# Power.net
KiCad netlist of a schematic drawn in Altium Designer
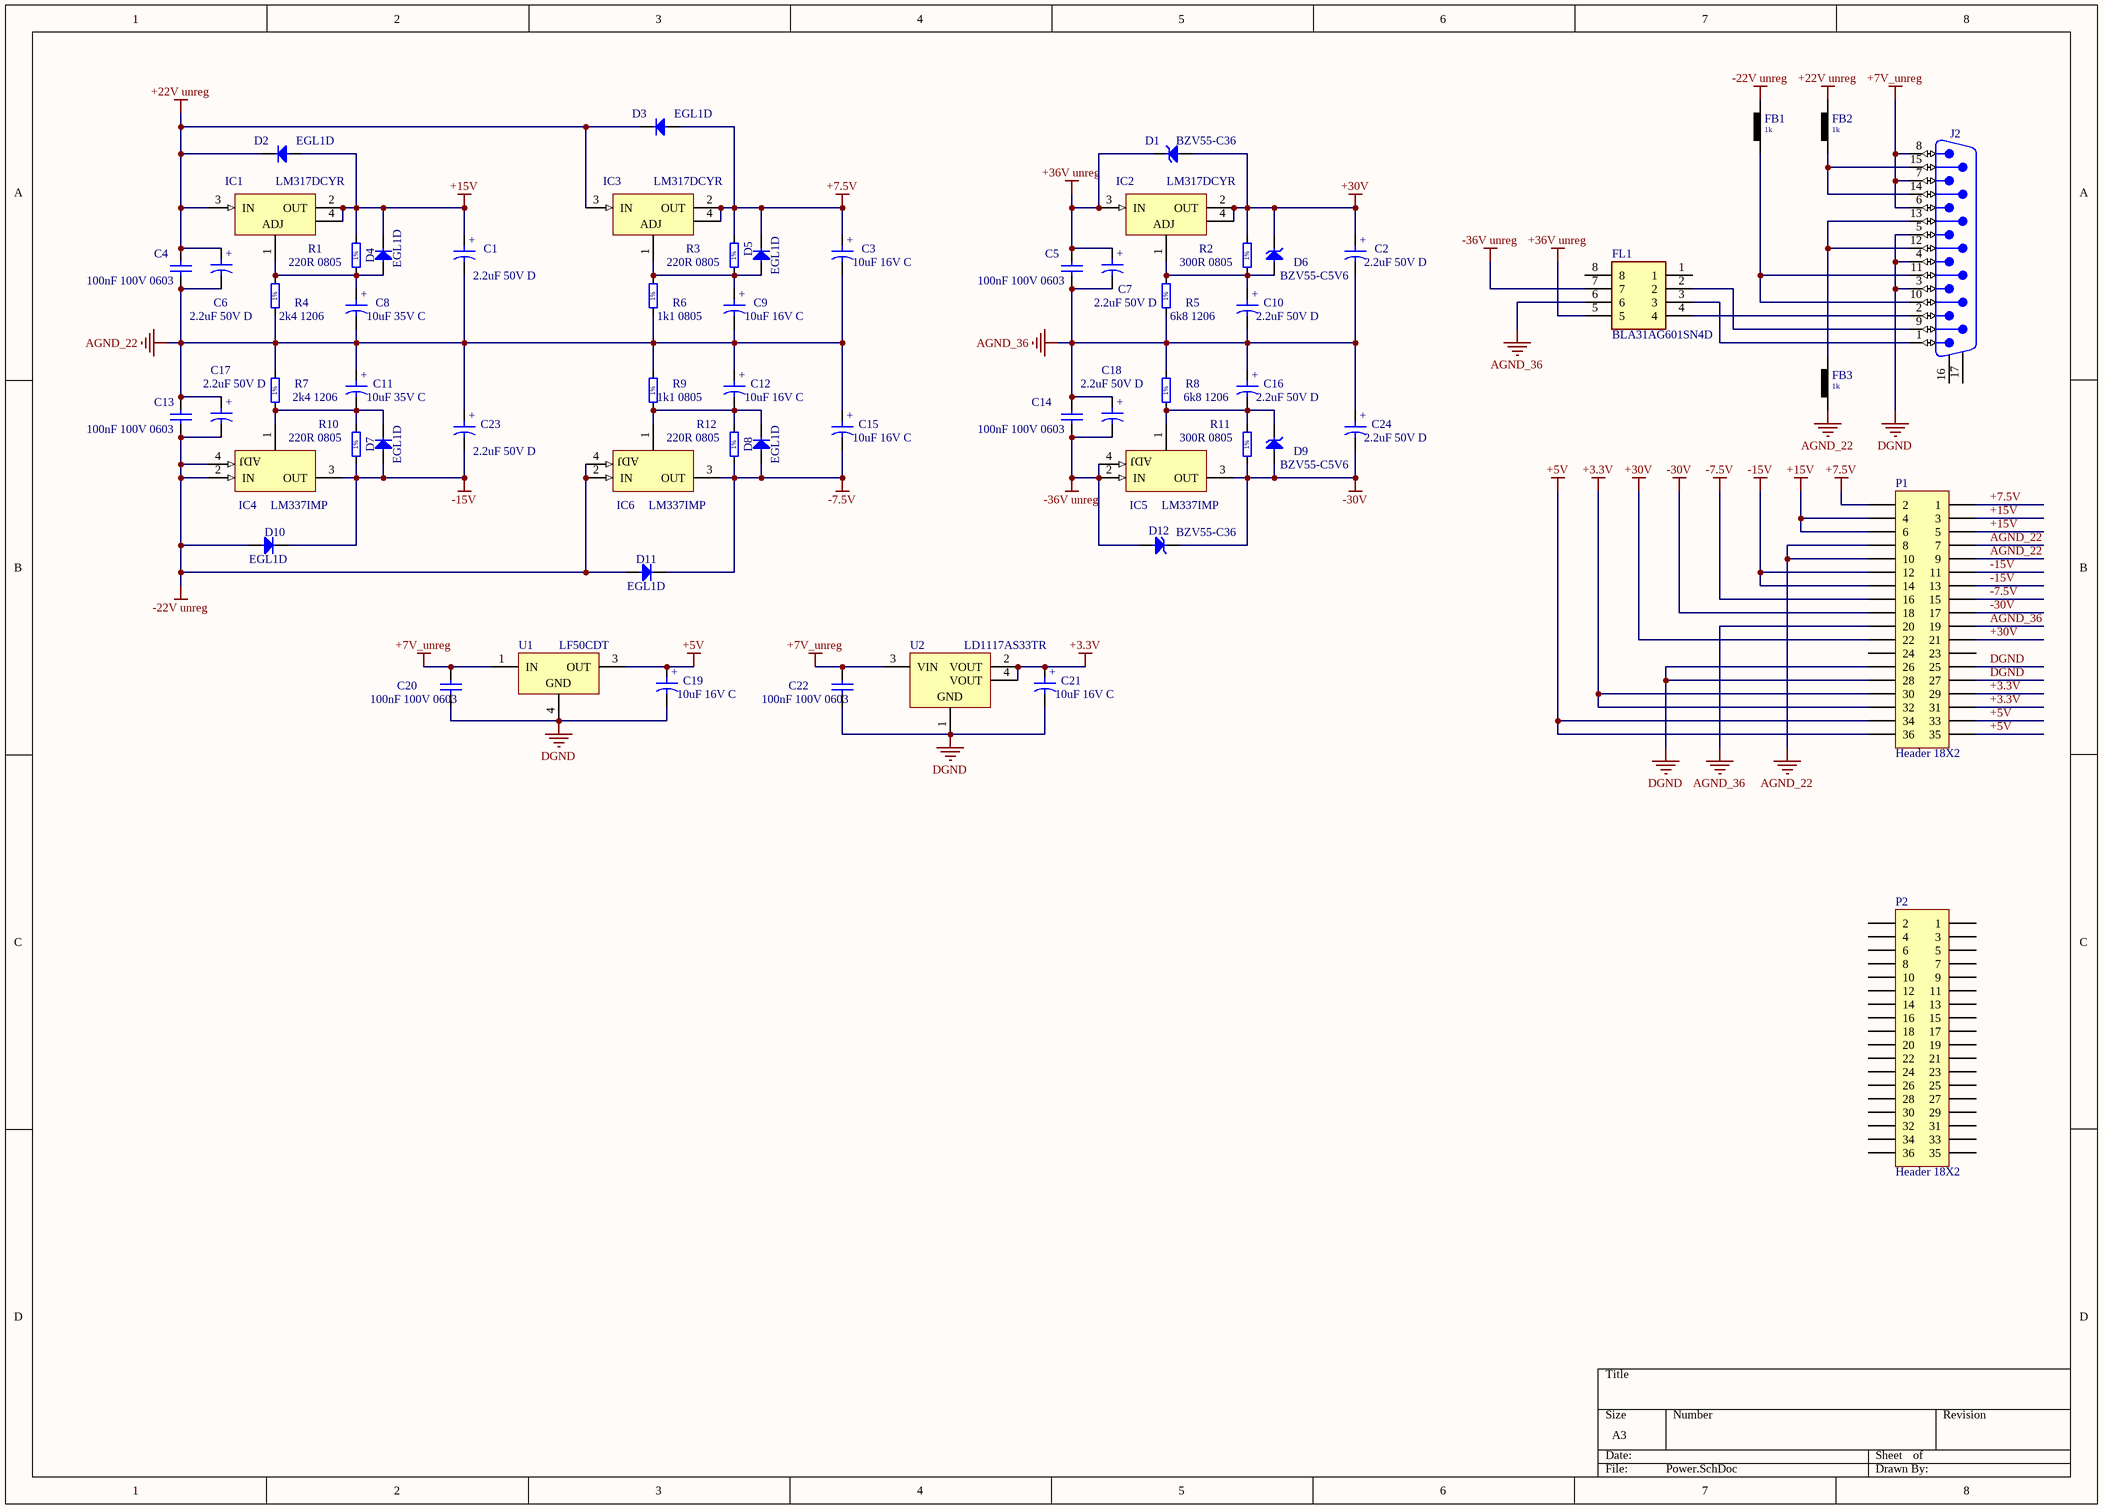
[diagram p0: Power.SchDoc]

(export (version "E")
  (design (tool "Eeschema 10.0.6"))
  (components
    (comp (ref "C1")
      (value "2.2uF 50V D")
      (footprint "CAPMP7343X310N")
      (description "Polarised capacitor")
      (fields
        (field (name "PART NUMBER") "CTE7343-31_22UF_35V_20%_LESR0400")
        (field (name "VOLTAGE") "35V")
        (field (name "AUTHOR") "CERN DEM MR")
      )
      (libsource (lib "Capacitors") (part "Capacitor - polarized"))
    )
    (comp (ref "C2")
      (value "2.2uF 50V D")
      (footprint "CAPMP7343X310N")
      (description "Polarised capacitor")
      (fields
        (field (name "PART NUMBER") "CTE7343-31_22UF_35V_20%_LESR0400")
        (field (name "VOLTAGE") "35V")
        (field (name "AUTHOR") "CERN DEM MR")
      )
      (libsource (lib "Capacitors") (part "Capacitor - polarized"))
    )
    (comp (ref "C3")
      (value "10uF 16V C")
      (footprint "CAPMP6032X280N")
      (description "Polarised capacitor")
      (fields
        (field (name "PART NUMBER") "CTE6032-28_10UF_25V_10%_LESR0500")
        (field (name "VOLTAGE") "25V")
        (field (name "AUTHOR") "CERN DEM JLC")
      )
      (libsource (lib "Capacitors") (part "Capacitor - polarized"))
    )
    (comp (ref "C4")
      (value "100nF 100V 0603")
      (footprint "1608[0603]_CAP")
      (description "Capacitor (Semiconductor SIM Model)")
      (fields (field (name "PUBLISHER") "Altium Limited"))
      (libsource (lib "Miscellaneous Devices") (part "Cap Semi"))
    )
    (comp (ref "C5")
      (value "100nF 100V 0603")
      (footprint "1608[0603]_CAP")
      (description "Capacitor (Semiconductor SIM Model)")
      (fields (field (name "PUBLISHER") "Altium Limited"))
      (libsource (lib "Miscellaneous Devices") (part "Cap Semi"))
    )
    (comp (ref "C6")
      (value "2.2uF 50V D")
      (footprint "CAPMP7343X310N")
      (description "Polarised capacitor")
      (fields
        (field (name "PART NUMBER") "CTE7343-31_22UF_35V_20%_LESR0400")
        (field (name "VOLTAGE") "35V")
        (field (name "AUTHOR") "CERN DEM MR")
      )
      (libsource (lib "Capacitors") (part "Capacitor - polarized"))
    )
    (comp (ref "C7")
      (value "2.2uF 50V D")
      (footprint "CAPMP7343X310N")
      (description "Polarised capacitor")
      (fields
        (field (name "PART NUMBER") "CTE7343-31_22UF_35V_20%_LESR0400")
        (field (name "VOLTAGE") "35V")
        (field (name "AUTHOR") "CERN DEM MR")
      )
      (libsource (lib "Capacitors") (part "Capacitor - polarized"))
    )
    (comp (ref "C8")
      (value "10uF 35V C")
      (footprint "CAPMP6032X280N")
      (description "Polarised capacitor")
      (fields
        (field (name "PART NUMBER") "CTE6032-28_10UF_25V_10%_LESR0500")
        (field (name "VOLTAGE") "25V")
        (field (name "AUTHOR") "CERN DEM JLC")
      )
      (libsource (lib "Capacitors") (part "Capacitor - polarized"))
    )
    (comp (ref "C9")
      (value "10uF 16V C")
      (footprint "CAPMP6032X280N")
      (description "Polarised capacitor")
      (fields
        (field (name "PART NUMBER") "CTE6032-28_10UF_25V_10%_LESR0500")
        (field (name "VOLTAGE") "25V")
        (field (name "AUTHOR") "CERN DEM JLC")
      )
      (libsource (lib "Capacitors") (part "Capacitor - polarized"))
    )
    (comp (ref "C10")
      (value "2.2uF 50V D")
      (footprint "CAPMP7343X310N")
      (description "Polarised capacitor")
      (fields
        (field (name "PART NUMBER") "CTE7343-31_22UF_35V_20%_LESR0400")
        (field (name "VOLTAGE") "35V")
        (field (name "AUTHOR") "CERN DEM MR")
      )
      (libsource (lib "Capacitors") (part "Capacitor - polarized"))
    )
    (comp (ref "C11")
      (value "10uF 35V C")
      (footprint "CAPMP6032X280N")
      (description "Polarised capacitor")
      (fields
        (field (name "PART NUMBER") "CTE6032-28_10UF_25V_10%_LESR0500")
        (field (name "VOLTAGE") "25V")
        (field (name "AUTHOR") "CERN DEM JLC")
      )
      (libsource (lib "Capacitors") (part "Capacitor - polarized"))
    )
    (comp (ref "C12")
      (value "10uF 16V C")
      (footprint "CAPMP6032X280N")
      (description "Polarised capacitor")
      (fields
        (field (name "PART NUMBER") "CTE6032-28_10UF_25V_10%_LESR0500")
        (field (name "VOLTAGE") "25V")
        (field (name "AUTHOR") "CERN DEM JLC")
      )
      (libsource (lib "Capacitors") (part "Capacitor - polarized"))
    )
    (comp (ref "C13")
      (value "100nF 100V 0603")
      (footprint "1608[0603]_CAP")
      (description "Capacitor (Semiconductor SIM Model)")
      (fields (field (name "PUBLISHER") "Altium Limited"))
      (libsource (lib "Miscellaneous Devices") (part "Cap Semi"))
    )
    (comp (ref "C14")
      (value "100nF 100V 0603")
      (footprint "1608[0603]_CAP")
      (description "Capacitor (Semiconductor SIM Model)")
      (fields (field (name "PUBLISHER") "Altium Limited"))
      (libsource (lib "Miscellaneous Devices") (part "Cap Semi"))
    )
    (comp (ref "C15")
      (value "10uF 16V C")
      (footprint "CAPMP6032X280N")
      (description "Polarised capacitor")
      (fields
        (field (name "PART NUMBER") "CTE6032-28_10UF_25V_10%_LESR0500")
        (field (name "VOLTAGE") "25V")
        (field (name "AUTHOR") "CERN DEM JLC")
      )
      (libsource (lib "Capacitors") (part "Capacitor - polarized"))
    )
    (comp (ref "C16")
      (value "2.2uF 50V D")
      (footprint "CAPMP7343X310N")
      (description "Polarised capacitor")
      (fields
        (field (name "PART NUMBER") "CTE7343-31_22UF_35V_20%_LESR0400")
        (field (name "VOLTAGE") "35V")
        (field (name "AUTHOR") "CERN DEM MR")
      )
      (libsource (lib "Capacitors") (part "Capacitor - polarized"))
    )
    (comp (ref "C17")
      (value "2.2uF 50V D")
      (footprint "CAPMP7343X310N")
      (description "Polarised capacitor")
      (fields
        (field (name "PART NUMBER") "CTE7343-31_22UF_35V_20%_LESR0400")
        (field (name "VOLTAGE") "35V")
        (field (name "AUTHOR") "CERN DEM MR")
      )
      (libsource (lib "Capacitors") (part "Capacitor - polarized"))
    )
    (comp (ref "C18")
      (value "2.2uF 50V D")
      (footprint "CAPMP7343X310N")
      (description "Polarised capacitor")
      (fields
        (field (name "PART NUMBER") "CTE7343-31_22UF_35V_20%_LESR0400")
        (field (name "VOLTAGE") "35V")
        (field (name "AUTHOR") "CERN DEM MR")
      )
      (libsource (lib "Capacitors") (part "Capacitor - polarized"))
    )
    (comp (ref "C19")
      (value "10uF 16V C")
      (footprint "CAPMP6032X280N")
      (description "Polarised capacitor")
      (fields
        (field (name "PART NUMBER") "CTE6032-28_10UF_25V_10%_LESR0500")
        (field (name "VOLTAGE") "25V")
        (field (name "AUTHOR") "CERN DEM JLC")
      )
      (libsource (lib "Capacitors") (part "Capacitor - polarized"))
    )
    (comp (ref "C20")
      (value "100nF 100V 0603")
      (footprint "1608[0603]_CAP")
      (description "Capacitor (Semiconductor SIM Model)")
      (fields (field (name "PUBLISHER") "Altium Limited"))
      (libsource (lib "Miscellaneous Devices") (part "Cap Semi"))
    )
    (comp (ref "C21")
      (value "10uF 16V C")
      (footprint "CAPMP6032X280N")
      (description "Polarised capacitor")
      (fields
        (field (name "PART NUMBER") "CTE6032-28_10UF_25V_10%_LESR0500")
        (field (name "VOLTAGE") "25V")
        (field (name "AUTHOR") "CERN DEM JLC")
      )
      (libsource (lib "Capacitors") (part "Capacitor - polarized"))
    )
    (comp (ref "C22")
      (value "100nF 100V 0603")
      (footprint "1608[0603]_CAP")
      (description "Capacitor (Semiconductor SIM Model)")
      (fields (field (name "PUBLISHER") "Altium Limited"))
      (libsource (lib "Miscellaneous Devices") (part "Cap Semi"))
    )
    (comp (ref "C23")
      (value "2.2uF 50V D")
      (footprint "CAPMP7343X310N")
      (description "Polarised capacitor")
      (fields
        (field (name "PART NUMBER") "CTE7343-31_22UF_35V_20%_LESR0400")
        (field (name "VOLTAGE") "35V")
        (field (name "AUTHOR") "CERN DEM MR")
      )
      (libsource (lib "Capacitors") (part "Capacitor - polarized"))
    )
    (comp (ref "C24")
      (value "2.2uF 50V D")
      (footprint "CAPMP7343X310N")
      (description "Polarised capacitor")
      (fields
        (field (name "PART NUMBER") "CTE7343-31_22UF_35V_20%_LESR0400")
        (field (name "VOLTAGE") "35V")
        (field (name "AUTHOR") "CERN DEM MR")
      )
      (libsource (lib "Capacitors") (part "Capacitor - polarized"))
    )
    (comp (ref "D1")
      (value "BZV55-C36")
      (footprint "DIOMELF3515N")
      (description "Zener Diode")
      (fields
        (field (name "PART NUMBER") "BZV55-C12")
        (field (name "VOLTAGE") "12V")
        (field (name "AUTHOR") "CERN DEM MR")
      )
      (libsource (lib "ICs And Semiconductors") (part "Diode Zener"))
    )
    (comp (ref "D2")
      (value "EGL1D")
      (footprint "DIOMELF3515N")
      (description "Diode")
      (fields
        (field (name "PART NUMBER") "PMLL4148L")
        (field (name "VOLTAGE") "75V")
        (field (name "AUTHOR") "CERN DEM JLC")
      )
      (libsource (lib "ICs And Semiconductors") (part "Diode"))
    )
    (comp (ref "D3")
      (value "EGL1D")
      (footprint "DIOMELF3515N")
      (description "Diode")
      (fields
        (field (name "PART NUMBER") "PMLL4148L")
        (field (name "VOLTAGE") "75V")
        (field (name "AUTHOR") "CERN DEM JLC")
      )
      (libsource (lib "ICs And Semiconductors") (part "Diode"))
    )
    (comp (ref "D4")
      (value "EGL1D")
      (footprint "DIOMELF3515N")
      (description "Diode")
      (fields
        (field (name "PART NUMBER") "PMLL4148L")
        (field (name "VOLTAGE") "75V")
        (field (name "AUTHOR") "CERN DEM JLC")
      )
      (libsource (lib "ICs And Semiconductors") (part "Diode"))
    )
    (comp (ref "D5")
      (value "EGL1D")
      (footprint "DIOMELF3515N")
      (description "Diode")
      (fields
        (field (name "PART NUMBER") "PMLL4148L")
        (field (name "VOLTAGE") "75V")
        (field (name "AUTHOR") "CERN DEM JLC")
      )
      (libsource (lib "ICs And Semiconductors") (part "Diode"))
    )
    (comp (ref "D6")
      (value "BZV55-C5V6")
      (footprint "DIOMELF3515N")
      (description "Zener Diode")
      (fields
        (field (name "PART NUMBER") "BZV55-C12")
        (field (name "VOLTAGE") "12V")
        (field (name "AUTHOR") "CERN DEM MR")
      )
      (libsource (lib "ICs And Semiconductors") (part "Diode Zener"))
    )
    (comp (ref "D7")
      (value "EGL1D")
      (footprint "DIOMELF3515N")
      (description "Diode")
      (fields
        (field (name "PART NUMBER") "PMLL4148L")
        (field (name "VOLTAGE") "75V")
        (field (name "AUTHOR") "CERN DEM JLC")
      )
      (libsource (lib "ICs And Semiconductors") (part "Diode"))
    )
    (comp (ref "D8")
      (value "EGL1D")
      (footprint "DIOMELF3515N")
      (description "Diode")
      (fields
        (field (name "PART NUMBER") "PMLL4148L")
        (field (name "VOLTAGE") "75V")
        (field (name "AUTHOR") "CERN DEM JLC")
      )
      (libsource (lib "ICs And Semiconductors") (part "Diode"))
    )
    (comp (ref "D9")
      (value "BZV55-C5V6")
      (footprint "DIOMELF3515N")
      (description "Zener Diode")
      (fields
        (field (name "PART NUMBER") "BZV55-C12")
        (field (name "VOLTAGE") "12V")
        (field (name "AUTHOR") "CERN DEM MR")
      )
      (libsource (lib "ICs And Semiconductors") (part "Diode Zener"))
    )
    (comp (ref "D10")
      (value "EGL1D")
      (footprint "DIOMELF3515N")
      (description "Diode")
      (fields
        (field (name "PART NUMBER") "PMLL4148L")
        (field (name "VOLTAGE") "75V")
        (field (name "AUTHOR") "CERN DEM JLC")
      )
      (libsource (lib "ICs And Semiconductors") (part "Diode"))
    )
    (comp (ref "D11")
      (value "EGL1D")
      (footprint "DIOMELF3515N")
      (description "Diode")
      (fields
        (field (name "PART NUMBER") "PMLL4148L")
        (field (name "VOLTAGE") "75V")
        (field (name "AUTHOR") "CERN DEM JLC")
      )
      (libsource (lib "ICs And Semiconductors") (part "Diode"))
    )
    (comp (ref "D12")
      (value "BZV55-C36")
      (footprint "DIOMELF3515N")
      (description "Zener Diode")
      (fields
        (field (name "PART NUMBER") "BZV55-C12")
        (field (name "VOLTAGE") "12V")
        (field (name "AUTHOR") "CERN DEM MR")
      )
      (libsource (lib "ICs And Semiconductors") (part "Diode Zener"))
    )
    (comp (ref "FB1")
      (value "1k")
      (footprint "FB1206")
      (description "1206 1.5A 0.08ohm")
      (libsource (lib "SMD-RCL") (part "Chip FB BLM31P"))
    )
    (comp (ref "FB2")
      (value "1k")
      (footprint "FB1206")
      (description "1206 1.5A 0.08ohm")
      (libsource (lib "SMD-RCL") (part "Chip FB BLM31P"))
    )
    (comp (ref "FB3")
      (value "1k")
      (footprint "FB1206")
      (description "1206 1.5A 0.08ohm")
      (libsource (lib "SMD-RCL") (part "Chip FB BLM31P"))
    )
    (comp (ref "FL1")
      (value "BLA31AG601SN4D")
      (footprint "SamacSys:BLA31AG102SN4D")
      (description "Filter")
      (fields (field (name "MOUSER PART NUMBER") "81-BLA3216A601SG4"))
      (libsource (lib "SamacSys") (part "BLA31AG601SN4D"))
    )
    (comp (ref "IC1")
      (value "LM317DCYR")
      (footprint "SOT230P700X180-4N")
      (description "3-Terminal Regulator 1=Adj 2=OUT 3=IN 4=OUT")
      (fields
        (field (name "PART NUMBER") "LM317EMP")
        (field (name "MANUFACTURER") "TEXAS INSTRUMENTS")
        (field (name "AUTHOR") "CERN DEM JLC")
      )
      (libsource (lib "ICs And Semiconductors") (part "REG3+1 1ADJ-2OUT-3IN+4OUT"))
    )
    (comp (ref "IC2")
      (value "LM317DCYR")
      (footprint "SOT230P700X180-4N")
      (description "3-Terminal Regulator 1=Adj 2=OUT 3=IN 4=OUT")
      (fields
        (field (name "PART NUMBER") "LM317EMP")
        (field (name "MANUFACTURER") "TEXAS INSTRUMENTS")
        (field (name "AUTHOR") "CERN DEM JLC")
      )
      (libsource (lib "ICs And Semiconductors") (part "REG3+1 1ADJ-2OUT-3IN+4OUT"))
    )
    (comp (ref "IC3")
      (value "LM317DCYR")
      (footprint "SOT230P700X180-4N")
      (description "3-Terminal Regulator 1=Adj 2=OUT 3=IN 4=OUT")
      (fields
        (field (name "PART NUMBER") "LM317EMP")
        (field (name "MANUFACTURER") "TEXAS INSTRUMENTS")
        (field (name "AUTHOR") "CERN DEM JLC")
      )
      (libsource (lib "ICs And Semiconductors") (part "REG3+1 1ADJ-2OUT-3IN+4OUT"))
    )
    (comp (ref "IC4")
      (value "LM337IMP")
      (footprint "SOT230P700X180-4N")
      (description "3-Terminal Regulator 1=Adj 2=IN 3=OUT 4=IN")
      (fields
        (field (name "PART NUMBER") "LM337IMP/NOPB")
        (field (name "MANUFACTURER") "TEXAS INSTRUMENTS")
        (field (name "AUTHOR") "CERN DEM JLC")
      )
      (libsource (lib "ICs And Semiconductors") (part "REG3+1 1ADJ-2IN-3OUT+4IN"))
    )
    (comp (ref "IC5")
      (value "LM337IMP")
      (footprint "SOT230P700X180-4N")
      (description "3-Terminal Regulator 1=Adj 2=IN 3=OUT 4=IN")
      (fields
        (field (name "PART NUMBER") "LM337IMP/NOPB")
        (field (name "MANUFACTURER") "TEXAS INSTRUMENTS")
        (field (name "AUTHOR") "CERN DEM JLC")
      )
      (libsource (lib "ICs And Semiconductors") (part "REG3+1 1ADJ-2IN-3OUT+4IN"))
    )
    (comp (ref "IC6")
      (value "LM337IMP")
      (footprint "SOT230P700X180-4N")
      (description "3-Terminal Regulator 1=Adj 2=IN 3=OUT 4=IN")
      (fields
        (field (name "PART NUMBER") "LM337IMP/NOPB")
        (field (name "MANUFACTURER") "TEXAS INSTRUMENTS")
        (field (name "AUTHOR") "CERN DEM JLC")
      )
      (libsource (lib "ICs And Semiconductors") (part "REG3+1 1ADJ-2IN-3OUT+4IN"))
    )
    (comp (ref "J2")
      (value "D-Sub")
      (footprint "DB15_PCB_AL;UMINIUM")
      (description "Connector D-sub 15 Male")
      (fields
        (field (name "PART NUMBER") "AMPHENOL_L117DFA15P1ATN")
        (field (name "MANUFACTURER") "AMPHENOL")
        (field (name "AUTHOR") "CERN DEM JLC")
      )
      (libsource (lib "Connectors") (part "Connector D-sub 15 Male"))
    )
    (comp (ref "P1")
      (value "Header 18X2")
      (footprint "18x2 header aluminium")
      (description "Header, 18-Pin, Dual row")
      (fields (field (name "PUBLISHER") "Altium Limited"))
      (libsource (lib "Miscellaneous Connectors") (part "Header 18X2"))
    )
    (comp (ref "P2")
      (value "Header 18X2")
      (footprint "18x2 header aluminium")
      (description "Header, 18-Pin, Dual row")
      (fields (field (name "PUBLISHER") "Altium Limited"))
      (libsource (lib "Miscellaneous Connectors") (part "Header 18X2"))
    )
    (comp (ref "R1")
      (value "220R 0805")
      (footprint "RESC2012X60N")
      (description "Resistor - 1%")
      (fields
        (field (name "PART NUMBER") "R0805_220R_1%_0.125W_100PPM")
        (field (name "POWER") "0.125W")
        (field (name "AUTHOR") "CERN DEM JLC")
      )
      (libsource (lib "Resistors") (part "Resistor - 1%"))
    )
    (comp (ref "R2")
      (value "300R 0805")
      (footprint "RESC2012X60N")
      (description "Resistor - 1%")
      (fields
        (field (name "PART NUMBER") "R0805_220R_1%_0.125W_100PPM")
        (field (name "POWER") "0.125W")
        (field (name "AUTHOR") "CERN DEM JLC")
      )
      (libsource (lib "Resistors") (part "Resistor - 1%"))
    )
    (comp (ref "R3")
      (value "220R 0805")
      (footprint "RESC2012X60N")
      (description "Resistor - 1%")
      (fields
        (field (name "PART NUMBER") "R0805_220R_1%_0.125W_100PPM")
        (field (name "POWER") "0.125W")
        (field (name "AUTHOR") "CERN DEM JLC")
      )
      (libsource (lib "Resistors") (part "Resistor - 1%"))
    )
    (comp (ref "R4")
      (value "2k4 1206")
      (footprint "RESC3216X65N")
      (description "Resistor - 1%")
      (fields
        (field (name "PART NUMBER") "R1206_2K4_1%_0.25W_100PPM")
        (field (name "POWER") "0.25W")
        (field (name "AUTHOR") "CERN DEM JLC")
      )
      (libsource (lib "Resistors") (part "Resistor - 1%"))
    )
    (comp (ref "R5")
      (value "6k8 1206")
      (footprint "RESC3216X65N")
      (description "Resistor - 1%")
      (fields
        (field (name "PART NUMBER") "R1206_2K4_1%_0.25W_100PPM")
        (field (name "POWER") "0.25W")
        (field (name "AUTHOR") "CERN DEM JLC")
      )
      (libsource (lib "Resistors") (part "Resistor - 1%"))
    )
    (comp (ref "R6")
      (value "1k1 0805")
      (footprint "RESC2012X60N")
      (description "Resistor - 1%")
      (fields
        (field (name "PART NUMBER") "R0805_1K1_1%_0.125W_100PPM")
        (field (name "POWER") "0.125W")
        (field (name "AUTHOR") "CERN DEM JLC")
      )
      (libsource (lib "Resistors") (part "Resistor - 1%"))
    )
    (comp (ref "R7")
      (value "2k4 1206")
      (footprint "RESC3216X65N")
      (description "Resistor - 1%")
      (fields
        (field (name "PART NUMBER") "R1206_2K4_1%_0.25W_100PPM")
        (field (name "POWER") "0.25W")
        (field (name "AUTHOR") "CERN DEM JLC")
      )
      (libsource (lib "Resistors") (part "Resistor - 1%"))
    )
    (comp (ref "R8")
      (value "6k8 1206")
      (footprint "RESC3216X65N")
      (description "Resistor - 1%")
      (fields
        (field (name "PART NUMBER") "R1206_2K4_1%_0.25W_100PPM")
        (field (name "POWER") "0.25W")
        (field (name "AUTHOR") "CERN DEM JLC")
      )
      (libsource (lib "Resistors") (part "Resistor - 1%"))
    )
    (comp (ref "R9")
      (value "1k1 0805")
      (footprint "RESC2012X60N")
      (description "Resistor - 1%")
      (fields
        (field (name "PART NUMBER") "R0805_1K1_1%_0.125W_100PPM")
        (field (name "POWER") "0.125W")
        (field (name "AUTHOR") "CERN DEM JLC")
      )
      (libsource (lib "Resistors") (part "Resistor - 1%"))
    )
    (comp (ref "R10")
      (value "220R 0805")
      (footprint "RESC2012X60N")
      (description "Resistor - 1%")
      (fields
        (field (name "PART NUMBER") "R0805_220R_1%_0.125W_100PPM")
        (field (name "POWER") "0.125W")
        (field (name "AUTHOR") "CERN DEM JLC")
      )
      (libsource (lib "Resistors") (part "Resistor - 1%"))
    )
    (comp (ref "R11")
      (value "300R 0805")
      (footprint "RESC2012X60N")
      (description "Resistor - 1%")
      (fields
        (field (name "PART NUMBER") "R0805_220R_1%_0.125W_100PPM")
        (field (name "POWER") "0.125W")
        (field (name "AUTHOR") "CERN DEM JLC")
      )
      (libsource (lib "Resistors") (part "Resistor - 1%"))
    )
    (comp (ref "R12")
      (value "220R 0805")
      (footprint "RESC2012X60N")
      (description "Resistor - 1%")
      (fields
        (field (name "PART NUMBER") "R0805_220R_1%_0.125W_100PPM")
        (field (name "POWER") "0.125W")
        (field (name "AUTHOR") "CERN DEM JLC")
      )
      (libsource (lib "Resistors") (part "Resistor - 1%"))
    )
    (comp (ref "U1")
      (value "LF50CDT")
      (footprint "TO-252")
      (description "500mA, Very Low Drop (0.45V) Voltage Regulator")
      (fields (field (name "PUBLISHER") "Altium Limited"))
      (libsource (lib "ST Power Mgt Voltage Regulator") (part "LF50CDT"))
    )
    (comp (ref "U2")
      (value "LD1117AS33TR")
      (footprint "SOT-223_N")
      (description "1A, Low Drop Positive Voltage Regulator, 3.3V, 4-Pin SOT-223, Tape and Reel")
      (libsource (lib "STMicroelectronics Power Management Linear Regulator") (part "LD1117AS33TR"))
    )
  )
  (nets
    (net (code "1") (name "+3.3V") (class "Default")
      (node (ref "C21") (pin "1") (pinfunction "1_1") (pintype "passive"))
      (node (ref "P1") (pin "29") (pinfunction "29_29") (pintype "passive"))
      (node (ref "P1") (pin "30") (pinfunction "30_30") (pintype "passive"))
      (node (ref "P1") (pin "31") (pinfunction "31_31") (pintype "passive"))
      (node (ref "P1") (pin "32") (pinfunction "32_32") (pintype "passive"))
      (node (ref "U2") (pin "2") (pinfunction "VOUT_2") (pintype "power_in"))
      (node (ref "U2") (pin "4") (pinfunction "VOUT_4") (pintype "power_in"))
    )
    (net (code "2") (name "+5V") (class "Default")
      (node (ref "C19") (pin "1") (pinfunction "1_1") (pintype "passive"))
      (node (ref "P1") (pin "33") (pinfunction "33_33") (pintype "passive"))
      (node (ref "P1") (pin "34") (pinfunction "34_34") (pintype "passive"))
      (node (ref "P1") (pin "35") (pinfunction "35_35") (pintype "passive"))
      (node (ref "P1") (pin "36") (pinfunction "36_36") (pintype "passive"))
      (node (ref "U1") (pin "3") (pinfunction "OUT_3") (pintype "power_in"))
    )
    (net (code "3") (name "+7.5V") (class "Default")
      (node (ref "C3") (pin "1") (pinfunction "1_1") (pintype "passive"))
      (node (ref "D3") (pin "2") (pinfunction "A_2") (pintype "passive"))
      (node (ref "D5") (pin "1") (pinfunction "C_1") (pintype "passive"))
      (node (ref "IC3") (pin "2") (pinfunction "OUT_2") (pintype "power_in"))
      (node (ref "IC3") (pin "4") (pinfunction "OUT_4") (pintype "power_in"))
      (node (ref "P1") (pin "1") (pinfunction "1_1") (pintype "passive"))
      (node (ref "P1") (pin "2") (pinfunction "2_2") (pintype "passive"))
      (node (ref "R3") (pin "2") (pinfunction "2_2") (pintype "passive"))
    )
    (net (code "4") (name "+7V_unreg") (class "Default")
      (node (ref "C20") (pin "1") (pinfunction "1_1") (pintype "passive"))
      (node (ref "C22") (pin "1") (pinfunction "1_1") (pintype "passive"))
      (node (ref "J2") (pin "6") (pinfunction "6_6") (pintype "bidirectional"))
      (node (ref "J2") (pin "7") (pinfunction "7_7") (pintype "bidirectional"))
      (node (ref "J2") (pin "8") (pinfunction "8_8") (pintype "bidirectional"))
      (node (ref "U1") (pin "1") (pinfunction "IN_1") (pintype "power_in"))
      (node (ref "U2") (pin "3") (pinfunction "VIN_3") (pintype "power_in"))
    )
    (net (code "5") (name "+15V") (class "Default")
      (node (ref "C1") (pin "1") (pinfunction "1_1") (pintype "passive"))
      (node (ref "D2") (pin "2") (pinfunction "A_2") (pintype "passive"))
      (node (ref "D4") (pin "1") (pinfunction "C_1") (pintype "passive"))
      (node (ref "IC1") (pin "2") (pinfunction "OUT_2") (pintype "power_in"))
      (node (ref "IC1") (pin "4") (pinfunction "OUT_4") (pintype "power_in"))
      (node (ref "P1") (pin "3") (pinfunction "3_3") (pintype "passive"))
      (node (ref "P1") (pin "4") (pinfunction "4_4") (pintype "passive"))
      (node (ref "P1") (pin "5") (pinfunction "5_5") (pintype "passive"))
      (node (ref "P1") (pin "6") (pinfunction "6_6") (pintype "passive"))
      (node (ref "R1") (pin "2") (pinfunction "2_2") (pintype "passive"))
    )
    (net (code "6") (name "+22V unreg") (class "Default")
      (node (ref "C4") (pin "1") (pinfunction "1_1") (pintype "passive"))
      (node (ref "C6") (pin "1") (pinfunction "1_1") (pintype "passive"))
      (node (ref "D2") (pin "1") (pinfunction "C_1") (pintype "passive"))
      (node (ref "D3") (pin "1") (pinfunction "C_1") (pintype "passive"))
      (node (ref "FB2") (pin "2") (pinfunction "2_2") (pintype "passive"))
      (node (ref "IC1") (pin "3") (pinfunction "IN_3") (pintype "input"))
      (node (ref "IC3") (pin "3") (pinfunction "IN_3") (pintype "input"))
    )
    (net (code "7") (name "+30V") (class "Default")
      (node (ref "C2") (pin "1") (pinfunction "1_1") (pintype "passive"))
      (node (ref "D1") (pin "2") (pinfunction "A_2") (pintype "passive"))
      (node (ref "D6") (pin "1") (pinfunction "C_1") (pintype "passive"))
      (node (ref "IC2") (pin "2") (pinfunction "OUT_2") (pintype "power_in"))
      (node (ref "IC2") (pin "4") (pinfunction "OUT_4") (pintype "power_in"))
      (node (ref "P1") (pin "21") (pinfunction "21_21") (pintype "passive"))
      (node (ref "P1") (pin "22") (pinfunction "22_22") (pintype "passive"))
      (node (ref "R2") (pin "2") (pinfunction "2_2") (pintype "passive"))
    )
    (net (code "8") (name "+36V unreg") (class "Default")
      (node (ref "C5") (pin "1") (pinfunction "1_1") (pintype "passive"))
      (node (ref "C7") (pin "1") (pinfunction "1_1") (pintype "passive"))
      (node (ref "D1") (pin "1") (pinfunction "C_1") (pintype "passive"))
      (node (ref "FL1") (pin "5") (pinfunction "5_5") (pintype "passive"))
      (node (ref "IC2") (pin "3") (pinfunction "IN_3") (pintype "input"))
    )
    (net (code "9") (name "-7.5V") (class "Default")
      (node (ref "C15") (pin "2") (pinfunction "2_2") (pintype "passive"))
      (node (ref "D11") (pin "1") (pinfunction "C_1") (pintype "passive"))
      (node (ref "D8") (pin "2") (pinfunction "A_2") (pintype "passive"))
      (node (ref "IC6") (pin "3") (pinfunction "OUT_3") (pintype "power_in"))
      (node (ref "P1") (pin "15") (pinfunction "15_15") (pintype "passive"))
      (node (ref "P1") (pin "16") (pinfunction "16_16") (pintype "passive"))
      (node (ref "R12") (pin "1") (pinfunction "1_1") (pintype "passive"))
    )
    (net (code "10") (name "-15V") (class "Default")
      (node (ref "C23") (pin "2") (pinfunction "2_2") (pintype "passive"))
      (node (ref "D10") (pin "1") (pinfunction "C_1") (pintype "passive"))
      (node (ref "D7") (pin "2") (pinfunction "A_2") (pintype "passive"))
      (node (ref "IC4") (pin "3") (pinfunction "OUT_3") (pintype "power_in"))
      (node (ref "P1") (pin "11") (pinfunction "11_11") (pintype "passive"))
      (node (ref "P1") (pin "12") (pinfunction "12_12") (pintype "passive"))
      (node (ref "P1") (pin "13") (pinfunction "13_13") (pintype "passive"))
      (node (ref "P1") (pin "14") (pinfunction "14_14") (pintype "passive"))
      (node (ref "R10") (pin "1") (pinfunction "1_1") (pintype "passive"))
    )
    (net (code "11") (name "-22V unreg") (class "Default")
      (node (ref "C13") (pin "2") (pinfunction "2_2") (pintype "passive"))
      (node (ref "C17") (pin "2") (pinfunction "2_2") (pintype "passive"))
      (node (ref "D10") (pin "2") (pinfunction "A_2") (pintype "passive"))
      (node (ref "D11") (pin "2") (pinfunction "A_2") (pintype "passive"))
      (node (ref "FB1") (pin "2") (pinfunction "2_2") (pintype "passive"))
      (node (ref "IC4") (pin "2") (pinfunction "IN_2") (pintype "input"))
      (node (ref "IC4") (pin "4") (pinfunction "IN_4") (pintype "input"))
      (node (ref "IC6") (pin "2") (pinfunction "IN_2") (pintype "input"))
      (node (ref "IC6") (pin "4") (pinfunction "IN_4") (pintype "input"))
    )
    (net (code "12") (name "-30V") (class "Default")
      (node (ref "C24") (pin "2") (pinfunction "2_2") (pintype "passive"))
      (node (ref "D12") (pin "1") (pinfunction "C_1") (pintype "passive"))
      (node (ref "D9") (pin "2") (pinfunction "A_2") (pintype "passive"))
      (node (ref "IC5") (pin "3") (pinfunction "OUT_3") (pintype "power_in"))
      (node (ref "P1") (pin "17") (pinfunction "17_17") (pintype "passive"))
      (node (ref "P1") (pin "18") (pinfunction "18_18") (pintype "passive"))
      (node (ref "R11") (pin "1") (pinfunction "1_1") (pintype "passive"))
    )
    (net (code "13") (name "-36V unreg") (class "Default")
      (node (ref "C14") (pin "2") (pinfunction "2_2") (pintype "passive"))
      (node (ref "C18") (pin "2") (pinfunction "2_2") (pintype "passive"))
      (node (ref "D12") (pin "2") (pinfunction "A_2") (pintype "passive"))
      (node (ref "FL1") (pin "7") (pinfunction "7_7") (pintype "passive"))
      (node (ref "IC5") (pin "2") (pinfunction "IN_2") (pintype "input"))
      (node (ref "IC5") (pin "4") (pinfunction "IN_4") (pintype "input"))
    )
    (net (code "14") (name "AGND_22") (class "Default")
      (node (ref "C1") (pin "2") (pinfunction "2_2") (pintype "passive"))
      (node (ref "C11") (pin "1") (pinfunction "1_1") (pintype "passive"))
      (node (ref "C12") (pin "1") (pinfunction "1_1") (pintype "passive"))
      (node (ref "C13") (pin "1") (pinfunction "1_1") (pintype "passive"))
      (node (ref "C15") (pin "1") (pinfunction "1_1") (pintype "passive"))
      (node (ref "C17") (pin "1") (pinfunction "1_1") (pintype "passive"))
      (node (ref "C23") (pin "1") (pinfunction "1_1") (pintype "passive"))
      (node (ref "C3") (pin "2") (pinfunction "2_2") (pintype "passive"))
      (node (ref "C4") (pin "2") (pinfunction "2_2") (pintype "passive"))
      (node (ref "C6") (pin "2") (pinfunction "2_2") (pintype "passive"))
      (node (ref "C8") (pin "2") (pinfunction "2_2") (pintype "passive"))
      (node (ref "C9") (pin "2") (pinfunction "2_2") (pintype "passive"))
      (node (ref "FB3") (pin "1") (pinfunction "1_1") (pintype "passive"))
      (node (ref "P1") (pin "10") (pinfunction "10_10") (pintype "passive"))
      (node (ref "P1") (pin "7") (pinfunction "7_7") (pintype "passive"))
      (node (ref "P1") (pin "8") (pinfunction "8_8") (pintype "passive"))
      (node (ref "P1") (pin "9") (pinfunction "9_9") (pintype "passive"))
      (node (ref "R4") (pin "1") (pinfunction "1_1") (pintype "passive"))
      (node (ref "R6") (pin "1") (pinfunction "1_1") (pintype "passive"))
      (node (ref "R7") (pin "2") (pinfunction "2_2") (pintype "passive"))
      (node (ref "R9") (pin "2") (pinfunction "2_2") (pintype "passive"))
    )
    (net (code "15") (name "AGND_36") (class "Default")
      (node (ref "C10") (pin "2") (pinfunction "2_2") (pintype "passive"))
      (node (ref "C14") (pin "1") (pinfunction "1_1") (pintype "passive"))
      (node (ref "C16") (pin "1") (pinfunction "1_1") (pintype "passive"))
      (node (ref "C18") (pin "1") (pinfunction "1_1") (pintype "passive"))
      (node (ref "C2") (pin "2") (pinfunction "2_2") (pintype "passive"))
      (node (ref "C24") (pin "1") (pinfunction "1_1") (pintype "passive"))
      (node (ref "C5") (pin "2") (pinfunction "2_2") (pintype "passive"))
      (node (ref "C7") (pin "2") (pinfunction "2_2") (pintype "passive"))
      (node (ref "FL1") (pin "6") (pinfunction "6_6") (pintype "passive"))
      (node (ref "P1") (pin "19") (pinfunction "19_19") (pintype "passive"))
      (node (ref "P1") (pin "20") (pinfunction "20_20") (pintype "passive"))
      (node (ref "R5") (pin "1") (pinfunction "1_1") (pintype "passive"))
      (node (ref "R8") (pin "2") (pinfunction "2_2") (pintype "passive"))
    )
    (net (code "16") (name "DGND") (class "Default")
      (node (ref "C19") (pin "2") (pinfunction "2_2") (pintype "passive"))
      (node (ref "C20") (pin "2") (pinfunction "2_2") (pintype "passive"))
      (node (ref "C21") (pin "2") (pinfunction "2_2") (pintype "passive"))
      (node (ref "C22") (pin "2") (pinfunction "2_2") (pintype "passive"))
      (node (ref "J2") (pin "3") (pinfunction "3_3") (pintype "bidirectional"))
      (node (ref "J2") (pin "4") (pinfunction "4_4") (pintype "bidirectional"))
      (node (ref "J2") (pin "5") (pinfunction "5_5") (pintype "bidirectional"))
      (node (ref "P1") (pin "25") (pinfunction "25_25") (pintype "passive"))
      (node (ref "P1") (pin "26") (pinfunction "26_26") (pintype "passive"))
      (node (ref "P1") (pin "27") (pinfunction "27_27") (pintype "passive"))
      (node (ref "P1") (pin "28") (pinfunction "28_28") (pintype "passive"))
      (node (ref "U1") (pin "4") (pinfunction "GND_4") (pintype "power_in"))
      (node (ref "U2") (pin "1") (pinfunction "GND_1") (pintype "power_in"))
    )
    (net (code "17") (name "Net-(D4-A)") (class "Default")
      (node (ref "C8") (pin "1") (pinfunction "1_1") (pintype "passive"))
      (node (ref "D4") (pin "2") (pinfunction "A_2") (pintype "passive"))
      (node (ref "IC1") (pin "1") (pinfunction "ADJ_1") (pintype "power_in"))
      (node (ref "R1") (pin "1") (pinfunction "1_1") (pintype "passive"))
      (node (ref "R4") (pin "2") (pinfunction "2_2") (pintype "passive"))
    )
    (net (code "18") (name "Net-(D5-A)") (class "Default")
      (node (ref "C9") (pin "1") (pinfunction "1_1") (pintype "passive"))
      (node (ref "D5") (pin "2") (pinfunction "A_2") (pintype "passive"))
      (node (ref "IC3") (pin "1") (pinfunction "ADJ_1") (pintype "power_in"))
      (node (ref "R3") (pin "1") (pinfunction "1_1") (pintype "passive"))
      (node (ref "R6") (pin "2") (pinfunction "2_2") (pintype "passive"))
    )
    (net (code "19") (name "Net-(D6-A)") (class "Default")
      (node (ref "C10") (pin "1") (pinfunction "1_1") (pintype "passive"))
      (node (ref "D6") (pin "2") (pinfunction "A_2") (pintype "passive"))
      (node (ref "IC2") (pin "1") (pinfunction "ADJ_1") (pintype "power_in"))
      (node (ref "R2") (pin "1") (pinfunction "1_1") (pintype "passive"))
      (node (ref "R5") (pin "2") (pinfunction "2_2") (pintype "passive"))
    )
    (net (code "20") (name "Net-(D7-C)") (class "Default")
      (node (ref "C11") (pin "2") (pinfunction "2_2") (pintype "passive"))
      (node (ref "D7") (pin "1") (pinfunction "C_1") (pintype "passive"))
      (node (ref "IC4") (pin "1") (pinfunction "ADJ_1") (pintype "power_in"))
      (node (ref "R10") (pin "2") (pinfunction "2_2") (pintype "passive"))
      (node (ref "R7") (pin "1") (pinfunction "1_1") (pintype "passive"))
    )
    (net (code "21") (name "Net-(D8-C)") (class "Default")
      (node (ref "C12") (pin "2") (pinfunction "2_2") (pintype "passive"))
      (node (ref "D8") (pin "1") (pinfunction "C_1") (pintype "passive"))
      (node (ref "IC6") (pin "1") (pinfunction "ADJ_1") (pintype "power_in"))
      (node (ref "R12") (pin "2") (pinfunction "2_2") (pintype "passive"))
      (node (ref "R9") (pin "1") (pinfunction "1_1") (pintype "passive"))
    )
    (net (code "22") (name "Net-(D9-C)") (class "Default")
      (node (ref "C16") (pin "2") (pinfunction "2_2") (pintype "passive"))
      (node (ref "D9") (pin "1") (pinfunction "C_1") (pintype "passive"))
      (node (ref "IC5") (pin "1") (pinfunction "ADJ_1") (pintype "power_in"))
      (node (ref "R11") (pin "2") (pinfunction "2_2") (pintype "passive"))
      (node (ref "R8") (pin "1") (pinfunction "1_1") (pintype "passive"))
    )
    (net (code "23") (name "Net-(FB1-Pad1)") (class "Default")
      (node (ref "FB1") (pin "1") (pinfunction "1_1") (pintype "passive"))
      (node (ref "J2") (pin "10") (pinfunction "10_10") (pintype "bidirectional"))
      (node (ref "J2") (pin "11") (pinfunction "11_11") (pintype "bidirectional"))
    )
    (net (code "24") (name "Net-(FB2-Pad1)") (class "Default")
      (node (ref "FB2") (pin "1") (pinfunction "1_1") (pintype "passive"))
      (node (ref "J2") (pin "14") (pinfunction "14_14") (pintype "bidirectional"))
      (node (ref "J2") (pin "15") (pinfunction "15_15") (pintype "bidirectional"))
    )
    (net (code "25") (name "Net-(FB3-Pad2)") (class "Default")
      (node (ref "FB3") (pin "2") (pinfunction "2_2") (pintype "passive"))
      (node (ref "J2") (pin "12") (pinfunction "12_12") (pintype "bidirectional"))
      (node (ref "J2") (pin "13") (pinfunction "13_13") (pintype "bidirectional"))
    )
    (net (code "26") (name "Net-(FL1-Pad2)") (class "Default")
      (node (ref "FL1") (pin "2") (pinfunction "2_2") (pintype "passive"))
      (node (ref "J2") (pin "9") (pinfunction "9_9") (pintype "bidirectional"))
    )
    (net (code "27") (name "Net-(FL1-Pad3)") (class "Default")
      (node (ref "FL1") (pin "3") (pinfunction "3_3") (pintype "passive"))
      (node (ref "J2") (pin "1") (pinfunction "1_1") (pintype "bidirectional"))
    )
    (net (code "28") (name "Net-(FL1-Pad4)") (class "Default")
      (node (ref "FL1") (pin "4") (pinfunction "4_4") (pintype "passive"))
      (node (ref "J2") (pin "2") (pinfunction "2_2") (pintype "bidirectional"))
    )
    (net (code "29") (name "unconnected-(FL1-Pad1)") (class "Default")
      (node (ref "FL1") (pin "1") (pinfunction "1_1") (pintype "passive"))
    )
    (net (code "30") (name "unconnected-(FL1-Pad8)") (class "Default")
      (node (ref "FL1") (pin "8") (pinfunction "8_8") (pintype "passive"))
    )
    (net (code "31") (name "unconnected-(J2-Pad16)") (class "Default")
      (node (ref "J2") (pin "16") (pinfunction "16_16") (pintype "passive"))
    )
    (net (code "32") (name "unconnected-(J2-Pad17)") (class "Default")
      (node (ref "J2") (pin "17") (pinfunction "17_17") (pintype "passive"))
    )
    (net (code "33") (name "unconnected-(P1-Pad23)") (class "Default")
      (node (ref "P1") (pin "23") (pinfunction "23_23") (pintype "passive"))
    )
    (net (code "34") (name "unconnected-(P1-Pad24)") (class "Default")
      (node (ref "P1") (pin "24") (pinfunction "24_24") (pintype "passive"))
    )
    (net (code "35") (name "unconnected-(P2-Pad1)") (class "Default")
      (node (ref "P2") (pin "1") (pinfunction "1_1") (pintype "passive"))
    )
    (net (code "36") (name "unconnected-(P2-Pad2)") (class "Default")
      (node (ref "P2") (pin "2") (pinfunction "2_2") (pintype "passive"))
    )
    (net (code "37") (name "unconnected-(P2-Pad3)") (class "Default")
      (node (ref "P2") (pin "3") (pinfunction "3_3") (pintype "passive"))
    )
    (net (code "38") (name "unconnected-(P2-Pad4)") (class "Default")
      (node (ref "P2") (pin "4") (pinfunction "4_4") (pintype "passive"))
    )
    (net (code "39") (name "unconnected-(P2-Pad5)") (class "Default")
      (node (ref "P2") (pin "5") (pinfunction "5_5") (pintype "passive"))
    )
    (net (code "40") (name "unconnected-(P2-Pad6)") (class "Default")
      (node (ref "P2") (pin "6") (pinfunction "6_6") (pintype "passive"))
    )
    (net (code "41") (name "unconnected-(P2-Pad7)") (class "Default")
      (node (ref "P2") (pin "7") (pinfunction "7_7") (pintype "passive"))
    )
    (net (code "42") (name "unconnected-(P2-Pad8)") (class "Default")
      (node (ref "P2") (pin "8") (pinfunction "8_8") (pintype "passive"))
    )
    (net (code "43") (name "unconnected-(P2-Pad9)") (class "Default")
      (node (ref "P2") (pin "9") (pinfunction "9_9") (pintype "passive"))
    )
    (net (code "44") (name "unconnected-(P2-Pad10)") (class "Default")
      (node (ref "P2") (pin "10") (pinfunction "10_10") (pintype "passive"))
    )
    (net (code "45") (name "unconnected-(P2-Pad11)") (class "Default")
      (node (ref "P2") (pin "11") (pinfunction "11_11") (pintype "passive"))
    )
    (net (code "46") (name "unconnected-(P2-Pad12)") (class "Default")
      (node (ref "P2") (pin "12") (pinfunction "12_12") (pintype "passive"))
    )
    (net (code "47") (name "unconnected-(P2-Pad13)") (class "Default")
      (node (ref "P2") (pin "13") (pinfunction "13_13") (pintype "passive"))
    )
    (net (code "48") (name "unconnected-(P2-Pad14)") (class "Default")
      (node (ref "P2") (pin "14") (pinfunction "14_14") (pintype "passive"))
    )
    (net (code "49") (name "unconnected-(P2-Pad15)") (class "Default")
      (node (ref "P2") (pin "15") (pinfunction "15_15") (pintype "passive"))
    )
    (net (code "50") (name "unconnected-(P2-Pad16)") (class "Default")
      (node (ref "P2") (pin "16") (pinfunction "16_16") (pintype "passive"))
    )
    (net (code "51") (name "unconnected-(P2-Pad17)") (class "Default")
      (node (ref "P2") (pin "17") (pinfunction "17_17") (pintype "passive"))
    )
    (net (code "52") (name "unconnected-(P2-Pad18)") (class "Default")
      (node (ref "P2") (pin "18") (pinfunction "18_18") (pintype "passive"))
    )
    (net (code "53") (name "unconnected-(P2-Pad19)") (class "Default")
      (node (ref "P2") (pin "19") (pinfunction "19_19") (pintype "passive"))
    )
    (net (code "54") (name "unconnected-(P2-Pad20)") (class "Default")
      (node (ref "P2") (pin "20") (pinfunction "20_20") (pintype "passive"))
    )
    (net (code "55") (name "unconnected-(P2-Pad21)") (class "Default")
      (node (ref "P2") (pin "21") (pinfunction "21_21") (pintype "passive"))
    )
    (net (code "56") (name "unconnected-(P2-Pad22)") (class "Default")
      (node (ref "P2") (pin "22") (pinfunction "22_22") (pintype "passive"))
    )
    (net (code "57") (name "unconnected-(P2-Pad23)") (class "Default")
      (node (ref "P2") (pin "23") (pinfunction "23_23") (pintype "passive"))
    )
    (net (code "58") (name "unconnected-(P2-Pad24)") (class "Default")
      (node (ref "P2") (pin "24") (pinfunction "24_24") (pintype "passive"))
    )
    (net (code "59") (name "unconnected-(P2-Pad25)") (class "Default")
      (node (ref "P2") (pin "25") (pinfunction "25_25") (pintype "passive"))
    )
    (net (code "60") (name "unconnected-(P2-Pad26)") (class "Default")
      (node (ref "P2") (pin "26") (pinfunction "26_26") (pintype "passive"))
    )
    (net (code "61") (name "unconnected-(P2-Pad27)") (class "Default")
      (node (ref "P2") (pin "27") (pinfunction "27_27") (pintype "passive"))
    )
    (net (code "62") (name "unconnected-(P2-Pad28)") (class "Default")
      (node (ref "P2") (pin "28") (pinfunction "28_28") (pintype "passive"))
    )
    (net (code "63") (name "unconnected-(P2-Pad29)") (class "Default")
      (node (ref "P2") (pin "29") (pinfunction "29_29") (pintype "passive"))
    )
    (net (code "64") (name "unconnected-(P2-Pad30)") (class "Default")
      (node (ref "P2") (pin "30") (pinfunction "30_30") (pintype "passive"))
    )
    (net (code "65") (name "unconnected-(P2-Pad31)") (class "Default")
      (node (ref "P2") (pin "31") (pinfunction "31_31") (pintype "passive"))
    )
    (net (code "66") (name "unconnected-(P2-Pad32)") (class "Default")
      (node (ref "P2") (pin "32") (pinfunction "32_32") (pintype "passive"))
    )
    (net (code "67") (name "unconnected-(P2-Pad33)") (class "Default")
      (node (ref "P2") (pin "33") (pinfunction "33_33") (pintype "passive"))
    )
    (net (code "68") (name "unconnected-(P2-Pad34)") (class "Default")
      (node (ref "P2") (pin "34") (pinfunction "34_34") (pintype "passive"))
    )
    (net (code "69") (name "unconnected-(P2-Pad35)") (class "Default")
      (node (ref "P2") (pin "35") (pinfunction "35_35") (pintype "passive"))
    )
    (net (code "70") (name "unconnected-(P2-Pad36)") (class "Default")
      (node (ref "P2") (pin "36") (pinfunction "36_36") (pintype "passive"))
    )
  )
)
